# chipshouter-pico-mcu.net
KiCad netlist of a schematic drawn in Altium Designer
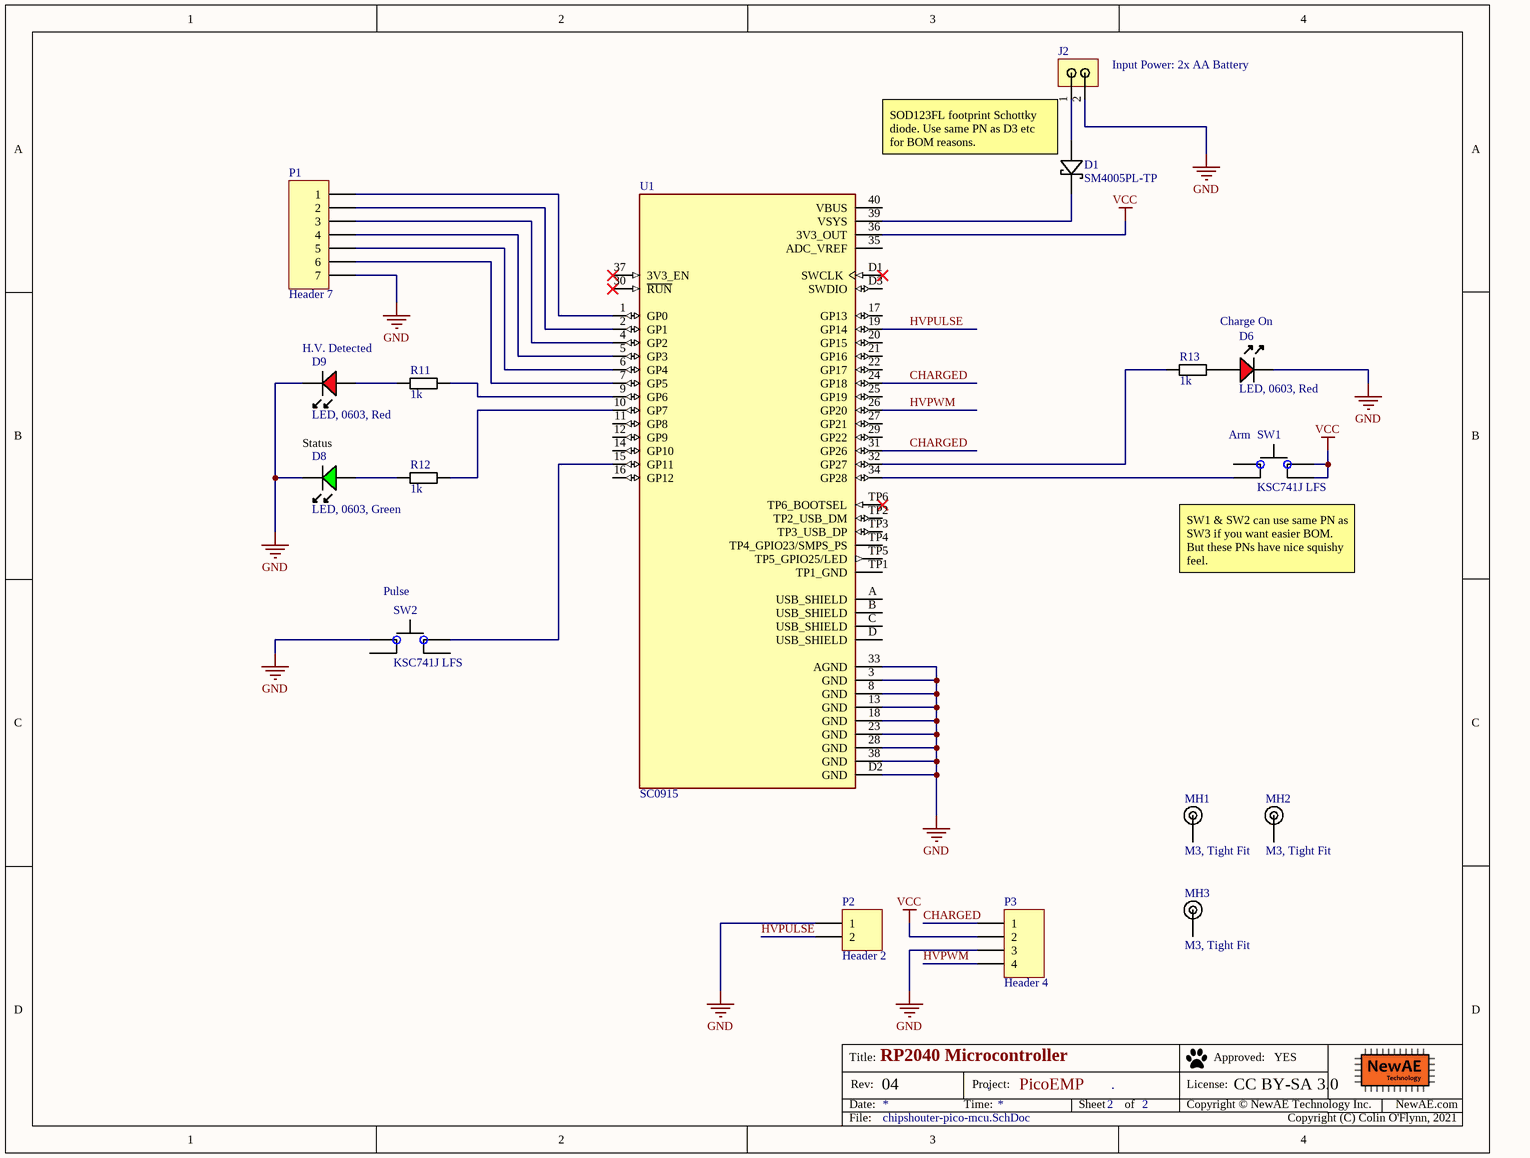
[diagram p0: chipshouter-pico-mcu.SchDoc]

(export (version "E")
  (design (tool "Eeschema 10.0.6"))
  (components
    (comp (ref "D1")
      (value "SM4005PL-TP")
      (footprint "DSS13UTR")
      (description "SCHOTTKY 30V SOD-123FL")
      (fields (field (name "PART NUMBER") "DSS13UTR"))
      (libsource (lib "NewAE_AltiumLib") (part "DIODE_SCHOTTKY"))
    )
    (comp (ref "D6")
      (value "LED, 0603, Red")
      (footprint "LED-0603-RED")
      (description "Chip LED, Red")
      (fields (field (name "PART NUMBER") "LEDCHIP_0603_RED"))
      (libsource (lib "NewAE_AltiumLib") (part "LED_RED"))
    )
    (comp (ref "D8")
      (value "LED, 0603, Green")
      (footprint "LED-0603-GREEN")
      (description "Chip LED, Green")
      (fields (field (name "PART NUMBER") "LEDCHIP_0603_GREEN"))
      (libsource (lib "NewAE_AltiumLib") (part "LED_GREEN"))
    )
    (comp (ref "D9")
      (value "LED, 0603, Red")
      (footprint "LED-0603-RED")
      (description "Chip LED, Red")
      (fields (field (name "PART NUMBER") "LEDCHIP_0603_RED"))
      (libsource (lib "NewAE_AltiumLib") (part "LED_RED"))
    )
    (comp (ref "J2")
      (value "1x2_Pin_Header")
      (footprint "22-23-2021")
      (description "CONN HEADER 2POS .100 VERT TIN")
      (fields (field (name "PART NUMBER") "Molex_2_Pin"))
      (libsource (lib "NewAE_AltiumLib") (part "1x2_Pin_Header"))
    )
    (comp (ref "MH1")
      (value "M3, Tight Fit")
      (footprint "MOUNT_M3_TIGHT")
      (description "Machine screw M3 Mounting Hole")
      (fields (field (name "PART NUMBER") "MOUNT_M3_TIGHT"))
      (libsource (lib "NewAE_AltiumLib") (part "Mounting_Hole"))
    )
    (comp (ref "MH2")
      (value "M3, Tight Fit")
      (footprint "MOUNT_M3_TIGHT")
      (description "Machine screw M3 Mounting Hole")
      (fields (field (name "PART NUMBER") "MOUNT_M3_TIGHT"))
      (libsource (lib "NewAE_AltiumLib") (part "Mounting_Hole"))
    )
    (comp (ref "MH3")
      (value "M3, Tight Fit")
      (footprint "MOUNT_M3_TIGHT")
      (description "Machine screw M3 Mounting Hole")
      (fields (field (name "PART NUMBER") "MOUNT_M3_TIGHT"))
      (libsource (lib "NewAE_AltiumLib") (part "Mounting_Hole"))
    )
    (comp (ref "P1")
      (value "Header 7")
      (footprint "HDR1X7")
      (description "Header, 7-Pin")
      (fields (field (name "PUBLISHER") "Altium Limited"))
      (libsource (lib "Miscellaneous Connectors") (part "Header 7"))
    )
    (comp (ref "P2")
      (value "Header 2")
      (footprint "HDR1X2")
      (description "Header, 2-Pin")
      (fields (field (name "PUBLISHER") "Altium Limited"))
      (libsource (lib "Miscellaneous Connectors") (part "Header 2"))
    )
    (comp (ref "P3")
      (value "Header 4")
      (footprint "HDR1X4")
      (description "Header, 4-Pin")
      (fields (field (name "PUBLISHER") "Altium Limited"))
      (libsource (lib "Miscellaneous Connectors") (part "Header 4"))
    )
    (comp (ref "R11")
      (value "1k")
      (footprint "RESC1608X55N")
      (description "1k res, 0603, 1%, 1/10W")
      (fields (field (name "PART NUMBER") "RCHIP-1K-0603") (field (name "TOLERANCE") "1%"))
      (libsource (lib "") (part "RES-EU_1"))
    )
    (comp (ref "R12")
      (value "1k")
      (footprint "RESC1608X55N")
      (description "1k res, 0603, 1%, 1/10W")
      (fields (field (name "PART NUMBER") "RCHIP-1K-0603") (field (name "TOLERANCE") "1%"))
      (libsource (lib "") (part "RES-EU_1"))
    )
    (comp (ref "R13")
      (value "1k")
      (footprint "RESC1608X55N")
      (description "1k res, 0603, 1%, 1/10W")
      (fields (field (name "PART NUMBER") "RCHIP-1K-0603") (field (name "TOLERANCE") "1%"))
      (libsource (lib "NewAE_AltiumLib") (part "RES-EU"))
    )
    (comp (ref "SW1")
      (value "KSC741J LFS")
      (footprint "CK_KSC7J")
      (description "SWITCH TACTILE SPST-NO 0.01A 32V")
      (fields (field (name "PART NUMBER") "TACTSW-KSC741J"))
      (libsource (lib "NewAE_AltiumLib") (part "SW_PB_NO_4PIN_TACT"))
    )
    (comp (ref "SW2")
      (value "KSC741J LFS")
      (footprint "CK_KSC7J")
      (description "SWITCH TACTILE SPST-NO 0.01A 32V")
      (fields (field (name "PART NUMBER") "TACTSW-KSC741J"))
      (libsource (lib "NewAE_AltiumLib") (part "SW_PB_NO_4PIN_TACT"))
    )
    (comp (ref "U1")
      (value "SC0915")
      (footprint "MODULE_SC0915_TH")
      (description "Raspberry Pi Pico")
      (fields (field (name "MF") "Raspberry Pi"))
      (libsource (lib "NewAE_AltiumLib") (part "SC0915"))
    )
  )
  (nets
    (net (code "1") (name "/CHARGED") (class "Default")
      (node (ref "P3") (pin "1") (pinfunction "1_1") (pintype "passive"))
      (node (ref "U1") (pin "24") (pinfunction "GP18_24") (pintype "bidirectional"))
      (node (ref "U1") (pin "31") (pinfunction "GP26_31") (pintype "bidirectional"))
    )
    (net (code "2") (name "/HVPULSE") (class "Default")
      (node (ref "P2") (pin "2") (pinfunction "2_2") (pintype "passive"))
      (node (ref "U1") (pin "19") (pinfunction "GP14_19") (pintype "bidirectional"))
    )
    (net (code "3") (name "/HVPWM") (class "Default")
      (node (ref "P3") (pin "4") (pinfunction "4_4") (pintype "passive"))
      (node (ref "U1") (pin "26") (pinfunction "GP20_26") (pintype "bidirectional"))
    )
    (net (code "4") (name "GND") (class "Default")
      (node (ref "D6") (pin "K") (pinfunction "K_K") (pintype "passive"))
      (node (ref "D8") (pin "K") (pinfunction "K_K") (pintype "passive"))
      (node (ref "D9") (pin "K") (pinfunction "K_K") (pintype "passive"))
      (node (ref "J2") (pin "2") (pinfunction "2_2") (pintype "passive"))
      (node (ref "P1") (pin "7") (pinfunction "7_7") (pintype "passive"))
      (node (ref "P2") (pin "1") (pinfunction "1_1") (pintype "passive"))
      (node (ref "P3") (pin "3") (pinfunction "3_3") (pintype "passive"))
      (node (ref "SW2") (pin "1") (pinfunction "IN_1") (pintype "passive"))
      (node (ref "U1") (pin "13") (pinfunction "GND_13") (pintype "power_in"))
      (node (ref "U1") (pin "18") (pinfunction "GND_18") (pintype "power_in"))
      (node (ref "U1") (pin "23") (pinfunction "GND_23") (pintype "power_in"))
      (node (ref "U1") (pin "28") (pinfunction "GND_28") (pintype "power_in"))
      (node (ref "U1") (pin "3") (pinfunction "GND_3") (pintype "power_in"))
      (node (ref "U1") (pin "33") (pinfunction "AGND_33") (pintype "power_in"))
      (node (ref "U1") (pin "38") (pinfunction "GND_38") (pintype "power_in"))
      (node (ref "U1") (pin "8") (pinfunction "GND_8") (pintype "power_in"))
      (node (ref "U1") (pin "D2") (pinfunction "GND_D2") (pintype "power_in"))
    )
    (net (code "5") (name "Net-(D1-PadA)") (class "Default")
      (node (ref "D1") (pin "A") (pinfunction "A_A") (pintype "passive"))
      (node (ref "J2") (pin "1") (pinfunction "1_1") (pintype "passive"))
    )
    (net (code "6") (name "Net-(D6-PadA)") (class "Default")
      (node (ref "D6") (pin "A") (pinfunction "A_A") (pintype "passive"))
      (node (ref "R13") (pin "1") (pinfunction "1_1") (pintype "passive"))
    )
    (net (code "7") (name "Net-(D8-PadA)") (class "Default")
      (node (ref "D8") (pin "A") (pinfunction "A_A") (pintype "passive"))
      (node (ref "R12") (pin "1") (pinfunction "1_1") (pintype "passive"))
    )
    (net (code "8") (name "Net-(D9-PadA)") (class "Default")
      (node (ref "D9") (pin "A") (pinfunction "A_A") (pintype "passive"))
      (node (ref "R11") (pin "1") (pinfunction "1_1") (pintype "passive"))
    )
    (net (code "9") (name "Net-(U1-GP0)") (class "Default")
      (node (ref "P1") (pin "1") (pinfunction "1_1") (pintype "passive"))
      (node (ref "U1") (pin "1") (pinfunction "GP0_1") (pintype "bidirectional"))
    )
    (net (code "10") (name "Net-(U1-GP1)") (class "Default")
      (node (ref "P1") (pin "2") (pinfunction "2_2") (pintype "passive"))
      (node (ref "U1") (pin "2") (pinfunction "GP1_2") (pintype "bidirectional"))
    )
    (net (code "11") (name "Net-(U1-GP2)") (class "Default")
      (node (ref "P1") (pin "3") (pinfunction "3_3") (pintype "passive"))
      (node (ref "U1") (pin "4") (pinfunction "GP2_4") (pintype "bidirectional"))
    )
    (net (code "12") (name "Net-(U1-GP3)") (class "Default")
      (node (ref "P1") (pin "4") (pinfunction "4_4") (pintype "passive"))
      (node (ref "U1") (pin "5") (pinfunction "GP3_5") (pintype "bidirectional"))
    )
    (net (code "13") (name "Net-(U1-GP4)") (class "Default")
      (node (ref "P1") (pin "5") (pinfunction "5_5") (pintype "passive"))
      (node (ref "U1") (pin "6") (pinfunction "GP4_6") (pintype "bidirectional"))
    )
    (net (code "14") (name "Net-(U1-GP5)") (class "Default")
      (node (ref "P1") (pin "6") (pinfunction "6_6") (pintype "passive"))
      (node (ref "U1") (pin "7") (pinfunction "GP5_7") (pintype "bidirectional"))
    )
    (net (code "15") (name "Net-(U1-GP6)") (class "Default")
      (node (ref "R11") (pin "2") (pinfunction "2_2") (pintype "passive"))
      (node (ref "U1") (pin "9") (pinfunction "GP6_9") (pintype "bidirectional"))
    )
    (net (code "16") (name "Net-(U1-GP7)") (class "Default")
      (node (ref "R12") (pin "2") (pinfunction "2_2") (pintype "passive"))
      (node (ref "U1") (pin "10") (pinfunction "GP7_10") (pintype "bidirectional"))
    )
    (net (code "17") (name "Net-(U1-GP11)") (class "Default")
      (node (ref "SW2") (pin "2") (pinfunction "IN_2") (pintype "passive"))
      (node (ref "U1") (pin "15") (pinfunction "GP11_15") (pintype "bidirectional"))
    )
    (net (code "18") (name "Net-(U1-GP27)") (class "Default")
      (node (ref "R13") (pin "2") (pinfunction "2_2") (pintype "passive"))
      (node (ref "U1") (pin "32") (pinfunction "GP27_32") (pintype "bidirectional"))
    )
    (net (code "19") (name "Net-(U1-GP28)") (class "Default")
      (node (ref "SW1") (pin "4") (pinfunction "IN_4") (pintype "passive"))
      (node (ref "U1") (pin "34") (pinfunction "GP28_34") (pintype "bidirectional"))
    )
    (net (code "20") (name "Net-(U1-VSYS)") (class "Default")
      (node (ref "D1") (pin "K") (pinfunction "K_K") (pintype "passive"))
      (node (ref "U1") (pin "39") (pinfunction "VSYS_39") (pintype "power_in"))
    )
    (net (code "21") (name "VCC") (class "Default")
      (node (ref "P3") (pin "2") (pinfunction "2_2") (pintype "passive"))
      (node (ref "SW1") (pin "2") (pinfunction "IN_2") (pintype "passive"))
      (node (ref "SW1") (pin "3") (pinfunction "IN_3") (pintype "passive"))
      (node (ref "U1") (pin "36") (pinfunction "3V3_OUT_36") (pintype "power_in"))
    )
    (net (code "22") (name "unconnected-(MH1-Pad1)") (class "Default")
      (node (ref "MH1") (pin "1") (pinfunction "1_1") (pintype "passive"))
    )
    (net (code "23") (name "unconnected-(MH2-Pad1)") (class "Default")
      (node (ref "MH2") (pin "1") (pinfunction "1_1") (pintype "passive"))
    )
    (net (code "24") (name "unconnected-(MH3-Pad1)") (class "Default")
      (node (ref "MH3") (pin "1") (pinfunction "1_1") (pintype "passive"))
    )
    (net (code "25") (name "unconnected-(SW1-IN-Pad1)") (class "Default")
      (node (ref "SW1") (pin "1") (pinfunction "IN_1") (pintype "passive"))
    )
    (net (code "26") (name "unconnected-(SW2-IN-Pad3)") (class "Default")
      (node (ref "SW2") (pin "3") (pinfunction "IN_3") (pintype "passive"))
    )
    (net (code "27") (name "unconnected-(SW2-IN-Pad4)") (class "Default")
      (node (ref "SW2") (pin "4") (pinfunction "IN_4") (pintype "passive"))
    )
    (net (code "28") (name "unconnected-(U1-3V3_EN-Pad37)") (class "Default")
      (node (ref "U1") (pin "37") (pinfunction "3V3_EN_37") (pintype "input+no_connect"))
    )
    (net (code "29") (name "unconnected-(U1-ADC_VREF-Pad35)") (class "Default")
      (node (ref "U1") (pin "35") (pinfunction "ADC_VREF_35") (pintype "power_in"))
    )
    (net (code "30") (name "unconnected-(U1-GP8-Pad11)") (class "Default")
      (node (ref "U1") (pin "11") (pinfunction "GP8_11") (pintype "bidirectional"))
    )
    (net (code "31") (name "unconnected-(U1-GP9-Pad12)") (class "Default")
      (node (ref "U1") (pin "12") (pinfunction "GP9_12") (pintype "bidirectional"))
    )
    (net (code "32") (name "unconnected-(U1-GP10-Pad14)") (class "Default")
      (node (ref "U1") (pin "14") (pinfunction "GP10_14") (pintype "bidirectional"))
    )
    (net (code "33") (name "unconnected-(U1-GP12-Pad16)") (class "Default")
      (node (ref "U1") (pin "16") (pinfunction "GP12_16") (pintype "bidirectional"))
    )
    (net (code "34") (name "unconnected-(U1-GP13-Pad17)") (class "Default")
      (node (ref "U1") (pin "17") (pinfunction "GP13_17") (pintype "bidirectional"))
    )
    (net (code "35") (name "unconnected-(U1-GP15-Pad20)") (class "Default")
      (node (ref "U1") (pin "20") (pinfunction "GP15_20") (pintype "bidirectional"))
    )
    (net (code "36") (name "unconnected-(U1-GP16-Pad21)") (class "Default")
      (node (ref "U1") (pin "21") (pinfunction "GP16_21") (pintype "bidirectional"))
    )
    (net (code "37") (name "unconnected-(U1-GP17-Pad22)") (class "Default")
      (node (ref "U1") (pin "22") (pinfunction "GP17_22") (pintype "bidirectional"))
    )
    (net (code "38") (name "unconnected-(U1-GP19-Pad25)") (class "Default")
      (node (ref "U1") (pin "25") (pinfunction "GP19_25") (pintype "bidirectional"))
    )
    (net (code "39") (name "unconnected-(U1-GP21-Pad27)") (class "Default")
      (node (ref "U1") (pin "27") (pinfunction "GP21_27") (pintype "bidirectional"))
    )
    (net (code "40") (name "unconnected-(U1-GP22-Pad29)") (class "Default")
      (node (ref "U1") (pin "29") (pinfunction "GP22_29") (pintype "bidirectional"))
    )
    (net (code "41") (name "unconnected-(U1-SWCLK-PadD1)") (class "Default")
      (node (ref "U1") (pin "D1") (pinfunction "SWCLK_D1") (pintype "input+no_connect"))
    )
    (net (code "42") (name "unconnected-(U1-SWDIO-PadD3)") (class "Default")
      (node (ref "U1") (pin "D3") (pinfunction "SWDIO_D3") (pintype "bidirectional"))
    )
    (net (code "43") (name "unconnected-(U1-TP1_GND-PadTP1)") (class "Default")
      (node (ref "U1") (pin "TP1") (pinfunction "TP1_GND_TP1") (pintype "power_in"))
    )
    (net (code "44") (name "unconnected-(U1-TP2_USB_DM-PadTP2)") (class "Default")
      (node (ref "U1") (pin "TP2") (pinfunction "TP2_USB_DM_TP2") (pintype "bidirectional"))
    )
    (net (code "45") (name "unconnected-(U1-TP3_USB_DP-PadTP3)") (class "Default")
      (node (ref "U1") (pin "TP3") (pinfunction "TP3_USB_DP_TP3") (pintype "bidirectional"))
    )
    (net (code "46") (name "unconnected-(U1-TP4_GPIO23{slash}SMPS_PS-PadTP4)") (class "Default")
      (node (ref "U1") (pin "TP4") (pinfunction "TP4_GPIO23/SMPS_PS_TP4") (pintype "passive"))
    )
    (net (code "47") (name "unconnected-(U1-TP5_GPIO25{slash}LED-PadTP5)") (class "Default")
      (node (ref "U1") (pin "TP5") (pinfunction "TP5_GPIO25/LED_TP5") (pintype "output"))
    )
    (net (code "48") (name "unconnected-(U1-TP6_BOOTSEL-PadTP6)") (class "Default")
      (node (ref "U1") (pin "TP6") (pinfunction "TP6_BOOTSEL_TP6") (pintype "input+no_connect"))
    )
    (net (code "49") (name "unconnected-(U1-USB_SHIELD-PadA)") (class "Default")
      (node (ref "U1") (pin "A") (pinfunction "USB_SHIELD_A") (pintype "power_in"))
    )
    (net (code "50") (name "unconnected-(U1-USB_SHIELD-PadB)") (class "Default")
      (node (ref "U1") (pin "B") (pinfunction "USB_SHIELD_B") (pintype "power_in"))
    )
    (net (code "51") (name "unconnected-(U1-USB_SHIELD-PadC)") (class "Default")
      (node (ref "U1") (pin "C") (pinfunction "USB_SHIELD_C") (pintype "power_in"))
    )
    (net (code "52") (name "unconnected-(U1-USB_SHIELD-PadD)") (class "Default")
      (node (ref "U1") (pin "D") (pinfunction "USB_SHIELD_D") (pintype "power_in"))
    )
    (net (code "53") (name "unconnected-(U1-VBUS-Pad40)") (class "Default")
      (node (ref "U1") (pin "40") (pinfunction "VBUS_40") (pintype "power_in"))
    )
    (net (code "54") (name "unconnected-(U1-~{RUN}-Pad30)") (class "Default")
      (node (ref "U1") (pin "30") (pinfunction "~{RUN}_30") (pintype "input+no_connect"))
    )
  )
)
